# BNC_Shield_0_1-0_8_SMD.net
KiCad netlist of a schematic drawn in EAGLE
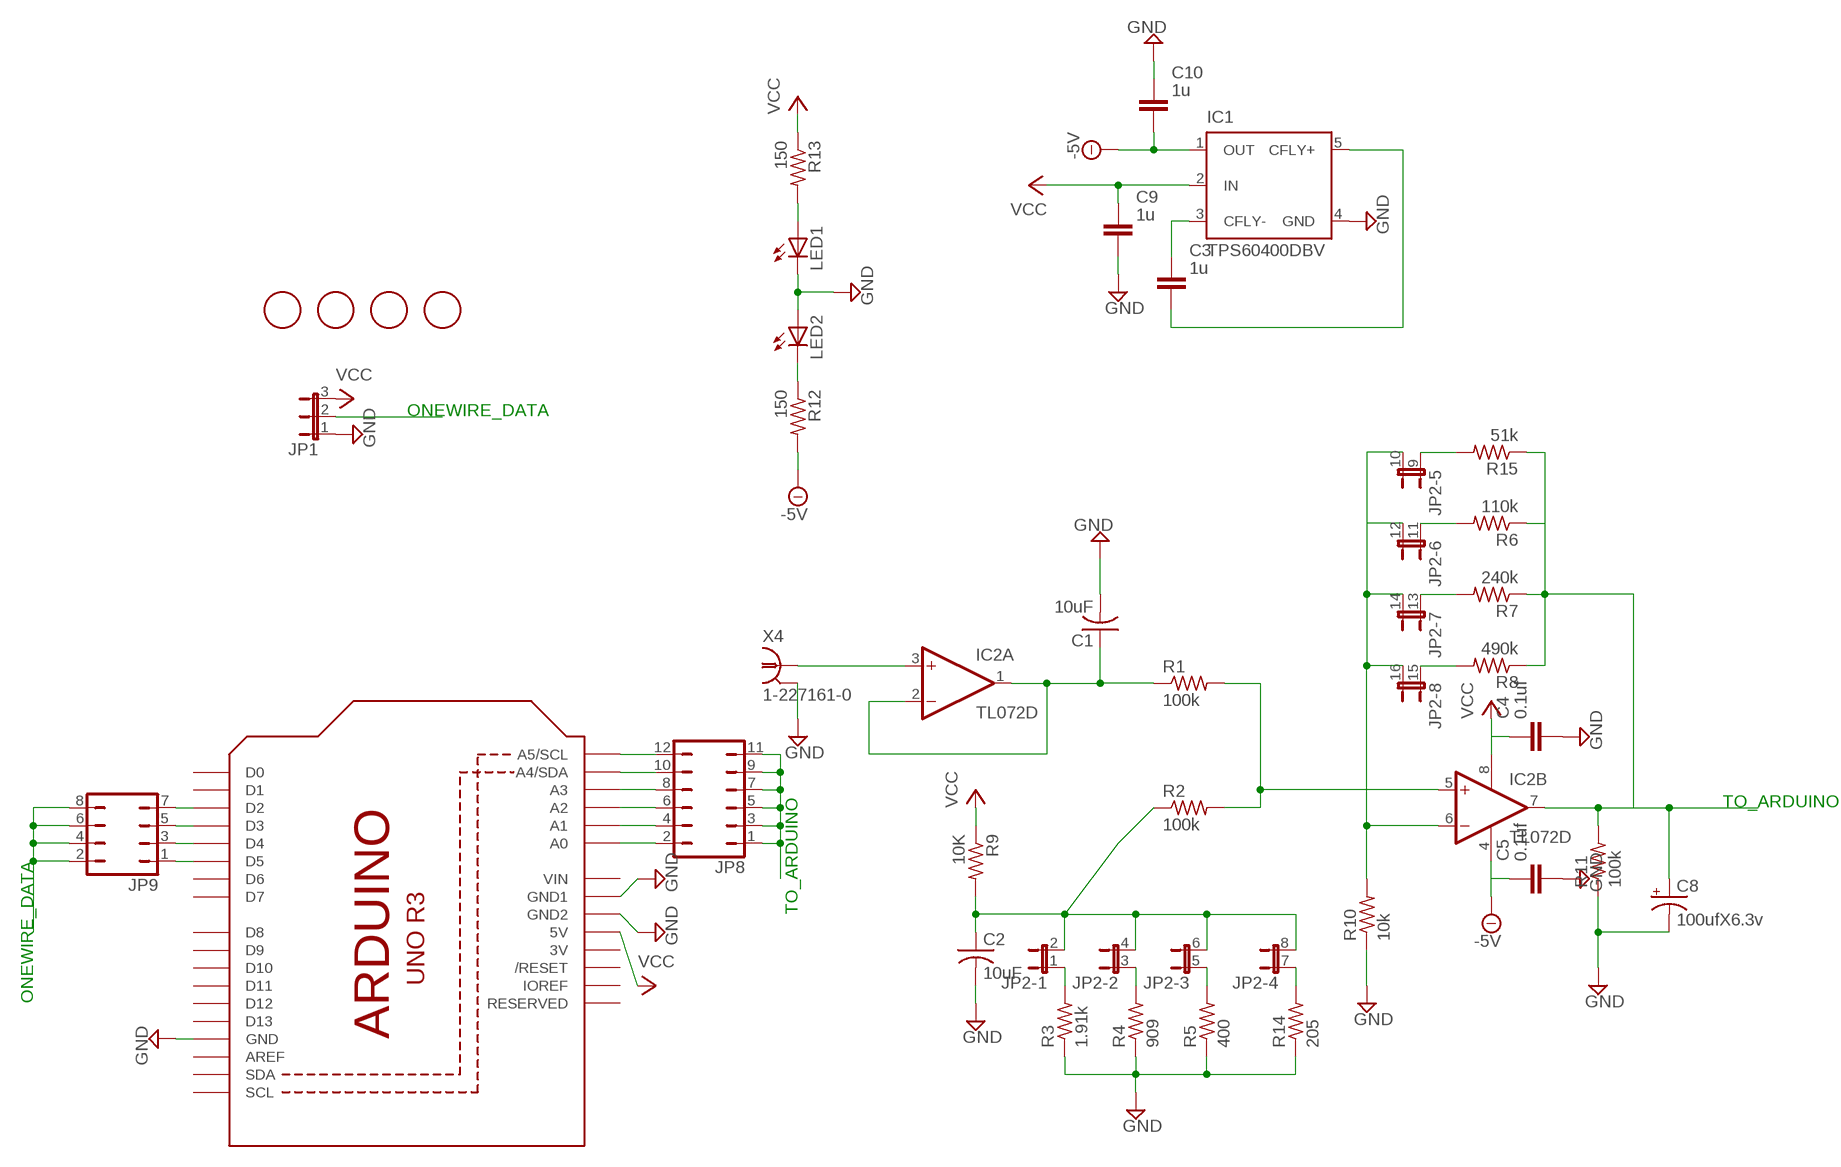
[diagram p0: schematic, sheet 1]

(export (version "E")
  (design (tool "Eeschema 10.0.6"))
  (components
    (comp (ref "C1")
      (value "10uF")
      (footprint "eagle-import:C0603")
      (libsource (lib "eagle-import") (part "C-USC0603"))
    )
    (comp (ref "C2")
      (value "10uF")
      (footprint "eagle-import:C0603")
      (libsource (lib "eagle-import") (part "C-USC0603"))
    )
    (comp (ref "C3")
      (value "1u")
      (footprint "eagle-import:C603")
      (libsource (lib "eagle-import") (part "CAPACITOR_NPOL-0603"))
    )
    (comp (ref "C4")
      (value "0.1uf")
      (footprint "eagle-import:C603")
      (libsource (lib "eagle-import") (part "CAPACITOR_NPOL-0603"))
    )
    (comp (ref "C5")
      (value "0.1uf")
      (footprint "eagle-import:C603")
      (libsource (lib "eagle-import") (part "CAPACITOR_NPOL-0603"))
    )
    (comp (ref "C8")
      (value "100ufX6.3v")
      (footprint "eagle-import:153CLV-0605")
      (libsource (lib "eagle-import") (part "CPOL-US153CLV-0605"))
    )
    (comp (ref "C9")
      (value "1u")
      (footprint "eagle-import:C603")
      (libsource (lib "eagle-import") (part "CAPACITOR_NPOL-0603"))
    )
    (comp (ref "C10")
      (value "1u")
      (footprint "eagle-import:C603")
      (libsource (lib "eagle-import") (part "CAPACITOR_NPOL-0603"))
    )
    (comp (ref "IC1")
      (value "TPS60400DBV")
      (footprint "eagle-import:SOT23-DBV")
      (libsource (lib "eagle-import") (part "TPS60400DBV"))
    )
    (comp (ref "IC2")
      (value "TL072D")
      (footprint "eagle-import:SO08")
      (libsource (lib "eagle-import") (part "TL072D"))
    )
    (comp (ref "JP1")
      (value "JP2E")
      (footprint "eagle-import:JP2")
      (libsource (lib "eagle-import") (part "JP2E"))
    )
    (comp (ref "JP2")
      (value "JP8QE")
      (footprint "eagle-import:JP8Q")
      (libsource (lib "eagle-import") (part "JP8QE"))
    )
    (comp (ref "JP8")
      (value "JP6Q")
      (footprint "eagle-import:JP6Q")
      (libsource (lib "eagle-import") (part "JP6Q"))
    )
    (comp (ref "JP9")
      (value "JP4Q")
      (footprint "eagle-import:JP4Q")
      (libsource (lib "eagle-import") (part "JP4Q"))
    )
    (comp (ref "LED1")
      (value "LEDCHIP-LED0603")
      (footprint "eagle-import:CHIP-LED0603")
      (libsource (lib "eagle-import") (part "LEDCHIP-LED0603"))
    )
    (comp (ref "LED2")
      (value "LEDCHIP-LED0603")
      (footprint "eagle-import:CHIP-LED0603")
      (libsource (lib "eagle-import") (part "LEDCHIP-LED0603"))
    )
    (comp (ref "R1")
      (value "100k")
      (footprint "eagle-import:R0603")
      (libsource (lib "eagle-import") (part "R-US_R0603"))
    )
    (comp (ref "R2")
      (value "100k")
      (footprint "eagle-import:R0603")
      (libsource (lib "eagle-import") (part "R-US_R0603"))
    )
    (comp (ref "R3")
      (value "1.91k")
      (footprint "eagle-import:R0603")
      (libsource (lib "eagle-import") (part "R-US_R0603"))
    )
    (comp (ref "R4")
      (value "909")
      (footprint "eagle-import:R0603")
      (libsource (lib "eagle-import") (part "R-US_R0603"))
    )
    (comp (ref "R5")
      (value "400")
      (footprint "eagle-import:R0603")
      (libsource (lib "eagle-import") (part "R-US_R0603"))
    )
    (comp (ref "R6")
      (value "110k")
      (footprint "eagle-import:R0603")
      (libsource (lib "eagle-import") (part "R-US_R0603"))
    )
    (comp (ref "R7")
      (value "240k")
      (footprint "eagle-import:R0603")
      (libsource (lib "eagle-import") (part "R-US_R0603"))
    )
    (comp (ref "R8")
      (value "490k")
      (footprint "eagle-import:R0603")
      (libsource (lib "eagle-import") (part "R-US_R0603"))
    )
    (comp (ref "R9")
      (value "10K")
      (footprint "eagle-import:R0603")
      (libsource (lib "eagle-import") (part "R-US_R0603"))
    )
    (comp (ref "R10")
      (value "10k")
      (footprint "eagle-import:R0603")
      (libsource (lib "eagle-import") (part "R-US_R0603"))
    )
    (comp (ref "R11")
      (value "100k")
      (footprint "eagle-import:R0603")
      (libsource (lib "eagle-import") (part "R-US_R0603"))
    )
    (comp (ref "R12")
      (value "150")
      (footprint "eagle-import:R0603")
      (libsource (lib "eagle-import") (part "R-US_R0603"))
    )
    (comp (ref "R13")
      (value "150")
      (footprint "eagle-import:R0603")
      (libsource (lib "eagle-import") (part "R-US_R0603"))
    )
    (comp (ref "R14")
      (value "205")
      (footprint "eagle-import:R0603")
      (libsource (lib "eagle-import") (part "R-US_R0603"))
    )
    (comp (ref "R15")
      (value "51k")
      (footprint "eagle-import:R0603")
      (libsource (lib "eagle-import") (part "R-US_R0603"))
    )
    (comp (ref "U$2")
      (value "FIDUCIAL")
      (footprint "eagle-import:FIDUCIAL_1MM")
      (libsource (lib "eagle-import") (part "FIDUCIAL"))
    )
    (comp (ref "U$3")
      (value "FIDUCIAL")
      (footprint "eagle-import:FIDUCIAL_1MM")
      (libsource (lib "eagle-import") (part "FIDUCIAL"))
    )
    (comp (ref "U$4")
      (value "FIDUCIAL")
      (footprint "eagle-import:FIDUCIAL_1MM")
      (libsource (lib "eagle-import") (part "FIDUCIAL"))
    )
    (comp (ref "U$5")
      (value "FIDUCIAL")
      (footprint "eagle-import:FIDUCIAL_1MM")
      (libsource (lib "eagle-import") (part "FIDUCIAL"))
    )
    (comp (ref "U1")
      (value "ARDUINOR3-DIMENSION")
      (footprint "eagle-import:ARDUINOR3")
      (libsource (lib "eagle-import") (part "ARDUINOR3-DIMENSION"))
    )
    (comp (ref "X4")
      (value "1-227161-0")
      (footprint "eagle-import:AMP_227161")
      (libsource (lib "eagle-import") (part "?2271611--0"))
    )
  )
  (nets
    (net (code "1") (name "-5V") (class "Default")
      (node (ref "C10") (pin "2") (pinfunction "2_2") (pintype "passive"))
      (node (ref "C5") (pin "1") (pinfunction "1_1") (pintype "passive"))
      (node (ref "IC1") (pin "1") (pinfunction "OUT_1") (pintype "input"))
      (node (ref "IC2") (pin "4") (pinfunction "V-_4") (pintype "power_in"))
      (node (ref "R12") (pin "2") (pinfunction "2_2") (pintype "passive"))
    )
    (net (code "2") (name "/3V") (class "Default")
      (node (ref "U1") (pin "3V") (pinfunction "3V_3V") (pintype "power_in"))
    )
    (net (code "3") (name "/ONEWIRE_DATA") (class "Default")
      (node (ref "JP1") (pin "2") (pinfunction "2_2") (pintype "passive"))
      (node (ref "JP9") (pin "2") (pinfunction "2_2") (pintype "passive"))
      (node (ref "JP9") (pin "4") (pinfunction "4_4") (pintype "passive"))
      (node (ref "JP9") (pin "6") (pinfunction "6_6") (pintype "passive"))
      (node (ref "JP9") (pin "8") (pinfunction "8_8") (pintype "passive"))
    )
    (net (code "4") (name "/TO_ARDUINO") (class "Default")
      (node (ref "C8") (pin "+") (pinfunction "+_+") (pintype "passive"))
      (node (ref "IC2") (pin "7") (pinfunction "OUT_7") (pintype "output"))
      (node (ref "JP8") (pin "1") (pinfunction "1_1") (pintype "passive"))
      (node (ref "JP8") (pin "11") (pinfunction "11_11") (pintype "passive"))
      (node (ref "JP8") (pin "3") (pinfunction "3_3") (pintype "passive"))
      (node (ref "JP8") (pin "5") (pinfunction "5_5") (pintype "passive"))
      (node (ref "JP8") (pin "7") (pinfunction "7_7") (pintype "passive"))
      (node (ref "JP8") (pin "9") (pinfunction "9_9") (pintype "passive"))
      (node (ref "R11") (pin "2") (pinfunction "2_2") (pintype "passive"))
      (node (ref "R15") (pin "1") (pinfunction "1_1") (pintype "passive"))
      (node (ref "R6") (pin "1") (pinfunction "1_1") (pintype "passive"))
      (node (ref "R7") (pin "1") (pinfunction "1_1") (pintype "passive"))
      (node (ref "R8") (pin "1") (pinfunction "1_1") (pintype "passive"))
    )
    (net (code "5") (name "/VIN") (class "Default")
      (node (ref "U1") (pin "VIN") (pinfunction "VIN_VIN") (pintype "power_in"))
    )
    (net (code "6") (name "GND") (class "Default")
      (node (ref "C1") (pin "2") (pinfunction "2_2") (pintype "passive"))
      (node (ref "C10") (pin "1") (pinfunction "1_1") (pintype "passive"))
      (node (ref "C2") (pin "2") (pinfunction "2_2") (pintype "passive"))
      (node (ref "C4") (pin "2") (pinfunction "2_2") (pintype "passive"))
      (node (ref "C5") (pin "2") (pinfunction "2_2") (pintype "passive"))
      (node (ref "C8") (pin "-") (pinfunction "-_-") (pintype "passive"))
      (node (ref "C9") (pin "2") (pinfunction "2_2") (pintype "passive"))
      (node (ref "IC1") (pin "4") (pinfunction "GND_4") (pintype "passive"))
      (node (ref "JP1") (pin "1") (pinfunction "1_1") (pintype "passive"))
      (node (ref "LED1") (pin "C") (pinfunction "C_C") (pintype "passive"))
      (node (ref "LED2") (pin "A") (pinfunction "A_A") (pintype "passive"))
      (node (ref "R10") (pin "1") (pinfunction "1_1") (pintype "passive"))
      (node (ref "R11") (pin "1") (pinfunction "1_1") (pintype "passive"))
      (node (ref "R14") (pin "1") (pinfunction "1_1") (pintype "passive"))
      (node (ref "R3") (pin "1") (pinfunction "1_1") (pintype "passive"))
      (node (ref "R4") (pin "1") (pinfunction "1_1") (pintype "passive"))
      (node (ref "R5") (pin "1") (pinfunction "1_1") (pintype "passive"))
      (node (ref "U1") (pin "GND") (pinfunction "GND_GND") (pintype "power_in"))
      (node (ref "U1") (pin "GND1") (pinfunction "GND1_GND1") (pintype "power_in"))
      (node (ref "U1") (pin "GND2") (pinfunction "GND2_GND2") (pintype "power_in"))
      (node (ref "X4") (pin "2") (pinfunction "GND_2") (pintype "power_in"))
    )
    (net (code "7") (name "Net-(IC1-CFLY+)") (class "Default")
      (node (ref "C3") (pin "2") (pinfunction "2_2") (pintype "passive"))
      (node (ref "IC1") (pin "5") (pinfunction "CFLY+_5") (pintype "passive"))
    )
    (net (code "8") (name "Net-(IC1-CFLY-)") (class "Default")
      (node (ref "C3") (pin "1") (pinfunction "1_1") (pintype "passive"))
      (node (ref "IC1") (pin "3") (pinfunction "CFLY-_3") (pintype "power_in"))
    )
    (net (code "9") (name "Net-(IC2A-+IN)") (class "Default")
      (node (ref "IC2") (pin "3") (pinfunction "+IN_3") (pintype "input"))
      (node (ref "X4") (pin "1") (pinfunction "1_1") (pintype "passive"))
    )
    (net (code "10") (name "Net-(IC2A--IN)") (class "Default")
      (node (ref "C1") (pin "1") (pinfunction "1_1") (pintype "passive"))
      (node (ref "IC2") (pin "1") (pinfunction "OUT_1") (pintype "output"))
      (node (ref "IC2") (pin "2") (pinfunction "-IN_2") (pintype "input"))
      (node (ref "R1") (pin "1") (pinfunction "1_1") (pintype "passive"))
    )
    (net (code "11") (name "Net-(IC2B-+IN)") (class "Default")
      (node (ref "IC2") (pin "5") (pinfunction "+IN_5") (pintype "input"))
      (node (ref "R1") (pin "2") (pinfunction "2_2") (pintype "passive"))
      (node (ref "R2") (pin "2") (pinfunction "2_2") (pintype "passive"))
    )
    (net (code "12") (name "Net-(IC2B--IN)") (class "Default")
      (node (ref "IC2") (pin "6") (pinfunction "-IN_6") (pintype "input"))
      (node (ref "JP2") (pin "10") (pinfunction "2_10") (pintype "passive"))
      (node (ref "JP2") (pin "12") (pinfunction "2_12") (pintype "passive"))
      (node (ref "JP2") (pin "14") (pinfunction "2_14") (pintype "passive"))
      (node (ref "JP2") (pin "16") (pinfunction "2_16") (pintype "passive"))
      (node (ref "R10") (pin "2") (pinfunction "2_2") (pintype "passive"))
    )
    (net (code "13") (name "Net-(JP2-Pad1)") (class "Default")
      (node (ref "JP2") (pin "1") (pinfunction "1_1") (pintype "passive"))
      (node (ref "R3") (pin "2") (pinfunction "2_2") (pintype "passive"))
    )
    (net (code "14") (name "Net-(JP2B-1)") (class "Default")
      (node (ref "JP2") (pin "3") (pinfunction "1_3") (pintype "passive"))
      (node (ref "R4") (pin "2") (pinfunction "2_2") (pintype "passive"))
    )
    (net (code "15") (name "Net-(JP2B-2)") (class "Default")
      (node (ref "C2") (pin "1") (pinfunction "1_1") (pintype "passive"))
      (node (ref "JP2") (pin "2") (pinfunction "2_2") (pintype "passive"))
      (node (ref "JP2") (pin "4") (pinfunction "2_4") (pintype "passive"))
      (node (ref "JP2") (pin "6") (pinfunction "2_6") (pintype "passive"))
      (node (ref "JP2") (pin "8") (pinfunction "2_8") (pintype "passive"))
      (node (ref "R2") (pin "1") (pinfunction "1_1") (pintype "passive"))
      (node (ref "R9") (pin "2") (pinfunction "2_2") (pintype "passive"))
    )
    (net (code "16") (name "Net-(JP2C-1)") (class "Default")
      (node (ref "JP2") (pin "5") (pinfunction "1_5") (pintype "passive"))
      (node (ref "R5") (pin "2") (pinfunction "2_2") (pintype "passive"))
    )
    (net (code "17") (name "Net-(JP2D-1)") (class "Default")
      (node (ref "JP2") (pin "7") (pinfunction "1_7") (pintype "passive"))
      (node (ref "R14") (pin "2") (pinfunction "2_2") (pintype "passive"))
    )
    (net (code "18") (name "Net-(JP2E-1)") (class "Default")
      (node (ref "JP2") (pin "9") (pinfunction "1_9") (pintype "passive"))
      (node (ref "R15") (pin "2") (pinfunction "2_2") (pintype "passive"))
    )
    (net (code "19") (name "Net-(JP2F-1)") (class "Default")
      (node (ref "JP2") (pin "11") (pinfunction "1_11") (pintype "passive"))
      (node (ref "R6") (pin "2") (pinfunction "2_2") (pintype "passive"))
    )
    (net (code "20") (name "Net-(JP2G-1)") (class "Default")
      (node (ref "JP2") (pin "13") (pinfunction "1_13") (pintype "passive"))
      (node (ref "R7") (pin "2") (pinfunction "2_2") (pintype "passive"))
    )
    (net (code "21") (name "Net-(JP2H-1)") (class "Default")
      (node (ref "JP2") (pin "15") (pinfunction "1_15") (pintype "passive"))
      (node (ref "R8") (pin "2") (pinfunction "2_2") (pintype "passive"))
    )
    (net (code "22") (name "Net-(JP8-Pad2)") (class "Default")
      (node (ref "JP8") (pin "2") (pinfunction "2_2") (pintype "passive"))
      (node (ref "U1") (pin "A0") (pinfunction "A0_A0") (pintype "bidirectional"))
    )
    (net (code "23") (name "Net-(JP8-Pad4)") (class "Default")
      (node (ref "JP8") (pin "4") (pinfunction "4_4") (pintype "passive"))
      (node (ref "U1") (pin "A1") (pinfunction "A1_A1") (pintype "bidirectional"))
    )
    (net (code "24") (name "Net-(JP8-Pad6)") (class "Default")
      (node (ref "JP8") (pin "6") (pinfunction "6_6") (pintype "passive"))
      (node (ref "U1") (pin "A2") (pinfunction "A2_A2") (pintype "bidirectional"))
    )
    (net (code "25") (name "Net-(JP8-Pad8)") (class "Default")
      (node (ref "JP8") (pin "8") (pinfunction "8_8") (pintype "passive"))
      (node (ref "U1") (pin "A3") (pinfunction "A3_A3") (pintype "bidirectional"))
    )
    (net (code "26") (name "Net-(JP9-Pad1)") (class "Default")
      (node (ref "JP9") (pin "1") (pinfunction "1_1") (pintype "passive"))
      (node (ref "U1") (pin "D5") (pinfunction "D5_D5") (pintype "bidirectional"))
    )
    (net (code "27") (name "Net-(JP9-Pad3)") (class "Default")
      (node (ref "JP9") (pin "3") (pinfunction "3_3") (pintype "passive"))
      (node (ref "U1") (pin "D4") (pinfunction "D4_D4") (pintype "bidirectional"))
    )
    (net (code "28") (name "Net-(JP9-Pad5)") (class "Default")
      (node (ref "JP9") (pin "5") (pinfunction "5_5") (pintype "passive"))
      (node (ref "U1") (pin "D3") (pinfunction "D3_D3") (pintype "bidirectional"))
    )
    (net (code "29") (name "Net-(JP9-Pad7)") (class "Default")
      (node (ref "JP9") (pin "7") (pinfunction "7_7") (pintype "passive"))
      (node (ref "U1") (pin "D2") (pinfunction "D2_D2") (pintype "bidirectional"))
    )
    (net (code "30") (name "Net-(LED1-PadA)") (class "Default")
      (node (ref "LED1") (pin "A") (pinfunction "A_A") (pintype "passive"))
      (node (ref "R13") (pin "2") (pinfunction "2_2") (pintype "passive"))
    )
    (net (code "31") (name "Net-(LED2-PadC)") (class "Default")
      (node (ref "LED2") (pin "C") (pinfunction "C_C") (pintype "passive"))
      (node (ref "R12") (pin "1") (pinfunction "1_1") (pintype "passive"))
    )
    (net (code "32") (name "Net-(U1-A4{slash}SDA)") (class "Default")
      (node (ref "JP8") (pin "10") (pinfunction "10_10") (pintype "passive"))
      (node (ref "U1") (pin "A4") (pinfunction "A4/SDA_A4") (pintype "bidirectional"))
    )
    (net (code "33") (name "Net-(U1-A5{slash}SCL)") (class "Default")
      (node (ref "JP8") (pin "12") (pinfunction "12_12") (pintype "passive"))
      (node (ref "U1") (pin "A5") (pinfunction "A5/SCL_A5") (pintype "bidirectional"))
    )
    (net (code "34") (name "VCC") (class "Default")
      (node (ref "C4") (pin "1") (pinfunction "1_1") (pintype "passive"))
      (node (ref "C9") (pin "1") (pinfunction "1_1") (pintype "passive"))
      (node (ref "IC1") (pin "2") (pinfunction "IN_2") (pintype "input"))
      (node (ref "IC2") (pin "8") (pinfunction "V+_8") (pintype "power_in"))
      (node (ref "JP1") (pin "3") (pinfunction "3_3") (pintype "passive"))
      (node (ref "R13") (pin "1") (pinfunction "1_1") (pintype "passive"))
      (node (ref "R9") (pin "1") (pinfunction "1_1") (pintype "passive"))
      (node (ref "U1") (pin "5V") (pinfunction "5V_5V") (pintype "power_in"))
    )
    (net (code "35") (name "unconnected-(U1-PadAREF)") (class "Default")
      (node (ref "U1") (pin "AREF") (pinfunction "AREF_AREF") (pintype "bidirectional"))
    )
    (net (code "36") (name "unconnected-(U1-PadD0)") (class "Default")
      (node (ref "U1") (pin "D0") (pinfunction "D0_D0") (pintype "bidirectional"))
    )
    (net (code "37") (name "unconnected-(U1-PadD1)") (class "Default")
      (node (ref "U1") (pin "D1") (pinfunction "D1_D1") (pintype "bidirectional"))
    )
    (net (code "38") (name "unconnected-(U1-PadD6)") (class "Default")
      (node (ref "U1") (pin "D6") (pinfunction "D6_D6") (pintype "bidirectional"))
    )
    (net (code "39") (name "unconnected-(U1-PadD7)") (class "Default")
      (node (ref "U1") (pin "D7") (pinfunction "D7_D7") (pintype "bidirectional"))
    )
    (net (code "40") (name "unconnected-(U1-PadD8)") (class "Default")
      (node (ref "U1") (pin "D8") (pinfunction "D8_D8") (pintype "bidirectional"))
    )
    (net (code "41") (name "unconnected-(U1-PadD9)") (class "Default")
      (node (ref "U1") (pin "D9") (pinfunction "D9_D9") (pintype "bidirectional"))
    )
    (net (code "42") (name "unconnected-(U1-PadD10)") (class "Default")
      (node (ref "U1") (pin "D10") (pinfunction "D10_D10") (pintype "bidirectional"))
    )
    (net (code "43") (name "unconnected-(U1-PadD11)") (class "Default")
      (node (ref "U1") (pin "D11") (pinfunction "D11_D11") (pintype "bidirectional"))
    )
    (net (code "44") (name "unconnected-(U1-PadD12)") (class "Default")
      (node (ref "U1") (pin "D12") (pinfunction "D12_D12") (pintype "bidirectional"))
    )
    (net (code "45") (name "unconnected-(U1-PadD13)") (class "Default")
      (node (ref "U1") (pin "D13") (pinfunction "D13_D13") (pintype "bidirectional"))
    )
    (net (code "46") (name "unconnected-(U1-PadIOREF)") (class "Default")
      (node (ref "U1") (pin "IOREF") (pinfunction "IOREF_IOREF") (pintype "output"))
    )
    (net (code "47") (name "unconnected-(U1-PadRESERVED)") (class "Default")
      (node (ref "U1") (pin "RESERVED") (pinfunction "RESERVED_RESERVED") (pintype "no_connect"))
    )
    (net (code "48") (name "unconnected-(U1-PadSCL)") (class "Default")
      (node (ref "U1") (pin "SCL") (pinfunction "SCL_SCL") (pintype "bidirectional"))
    )
    (net (code "49") (name "unconnected-(U1-PadSDA)") (class "Default")
      (node (ref "U1") (pin "SDA") (pinfunction "SDA_SDA") (pintype "bidirectional"))
    )
    (net (code "50") (name "unconnected-(U1-{slash}RESET-PadRESET)") (class "Default")
      (node (ref "U1") (pin "RESET") (pinfunction "/RESET_RESET") (pintype "bidirectional"))
    )
  )
)
